# PCB_Motor_Sheet1.net
KiCad netlist of a schematic drawn in Altium Designer
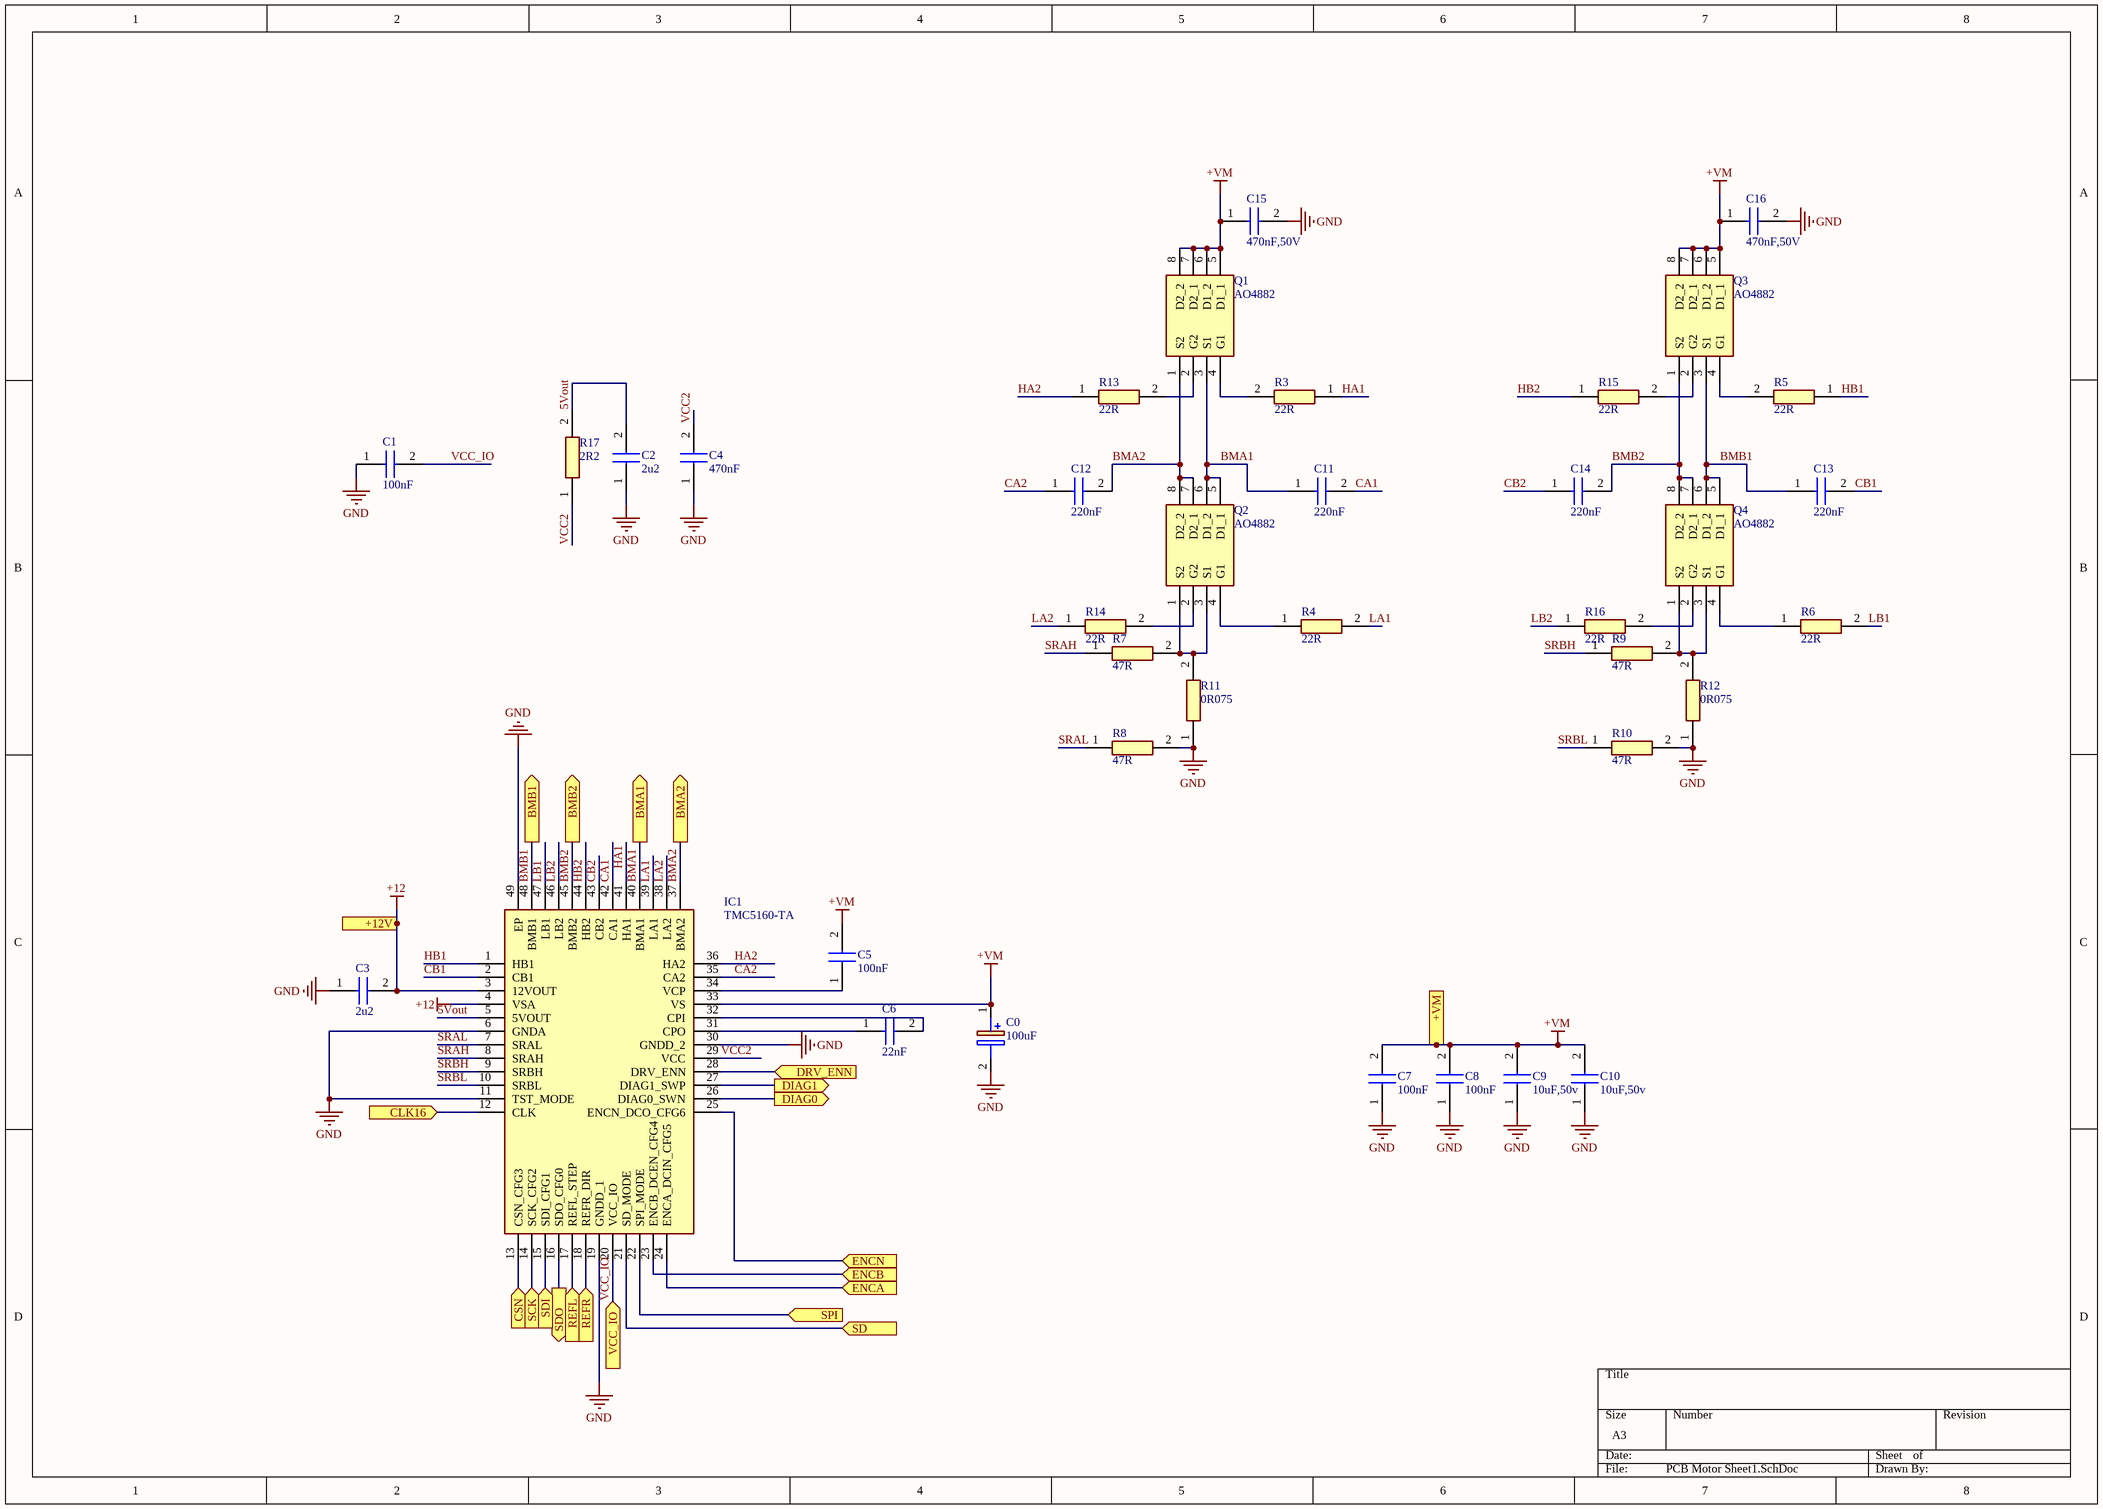
[diagram p0: PCB Motor Sheet1.SchDoc]

(export (version "E")
  (design (tool "Eeschema 10.0.6"))
  (components
    (comp (ref "C0")
      (value "100uF")
      (footprint "SamacSys:CAPAE850X1050N")
      (description "Capacitor Polarised\r\nMAL215097011E3")
      (fields
        (field (name "MANUFACTURER_PART_NUMBER") "MAL215097011E3")
        (field (name "MOUSER PART NUMBER") "594-MAL215097011E3")
      )
      (libsource (lib "*") (part "MAL215097011E3"))
    )
    (comp (ref "C1")
      (value "100nF")
      (footprint "SamacSys:CAPC1608X90N")
      (description "Capacitor")
      (fields
        (field (name "MANUFACTURER_PART_NUMBER") "GCM188R71H224KA64D")
        (field (name "MOUSER PART NUMBER") "81-GCM188R71H224K64D")
      )
      (libsource (lib "*") (part "GCM188R71H224KA64D"))
    )
    (comp (ref "C2")
      (value "2u2")
      (footprint "SamacSys:CAPC1608X90N")
      (description "Capacitor")
      (fields
        (field (name "MANUFACTURER_PART_NUMBER") "GCM188R71H224KA64D")
        (field (name "MOUSER PART NUMBER") "81-GCM188R71H224K64D")
      )
      (libsource (lib "*") (part "GCM188R71H224KA64D"))
    )
    (comp (ref "C3")
      (value "2u2")
      (footprint "SamacSys:CAPC1608X90N")
      (description "Capacitor")
      (fields
        (field (name "MANUFACTURER_PART_NUMBER") "GCM188R71H224KA64D")
        (field (name "MOUSER PART NUMBER") "81-GCM188R71H224K64D")
      )
      (libsource (lib "*") (part "GCM188R71H224KA64D"))
    )
    (comp (ref "C4")
      (value "470nF")
      (footprint "SamacSys:CAPC1608X90N")
      (description "Capacitor")
      (fields
        (field (name "MANUFACTURER_PART_NUMBER") "GCM188R71H224KA64D")
        (field (name "MOUSER PART NUMBER") "81-GCM188R71H224K64D")
      )
      (libsource (lib "*") (part "GCM188R71H224KA64D"))
    )
    (comp (ref "C5")
      (value "100nF")
      (footprint "SamacSys:CAPC1608X90N")
      (description "Capacitor")
      (fields
        (field (name "MANUFACTURER_PART_NUMBER") "GCM188R71H224KA64D")
        (field (name "MOUSER PART NUMBER") "81-GCM188R71H224K64D")
      )
      (libsource (lib "*") (part "GCM188R71H224KA64D"))
    )
    (comp (ref "C6")
      (value "22nF")
      (footprint "SamacSys:CAPC1608X90N")
      (description "Capacitor")
      (fields
        (field (name "MANUFACTURER_PART_NUMBER") "GCM188R71H224KA64D")
        (field (name "MOUSER PART NUMBER") "81-GCM188R71H224K64D")
      )
      (libsource (lib "*") (part "GCM188R71H224KA64D"))
    )
    (comp (ref "C7")
      (value "100nF")
      (footprint "SamacSys:CAPC1608X90N")
      (description "Capacitor")
      (fields
        (field (name "MANUFACTURER_PART_NUMBER") "GCM188R71H224KA64D")
        (field (name "MOUSER PART NUMBER") "81-GCM188R71H224K64D")
      )
      (libsource (lib "*") (part "GCM188R71H224KA64D"))
    )
    (comp (ref "C8")
      (value "100nF")
      (footprint "SamacSys:CAPC1608X90N")
      (description "Capacitor")
      (fields
        (field (name "MANUFACTURER_PART_NUMBER") "GCM188R71H224KA64D")
        (field (name "MOUSER PART NUMBER") "81-GCM188R71H224K64D")
      )
      (libsource (lib "*") (part "GCM188R71H224KA64D"))
    )
    (comp (ref "C9")
      (value "10uF,50v")
      (footprint "SamacSys:CAPC3216X180N")
      (description "Capacitor")
      (fields
        (field (name "MANUFACTURER_PART_NUMBER") "GRM31CR61H106MA12L")
        (field (name "MOUSER PART NUMBER") "81-GRM31CR61H106MA2L")
      )
      (libsource (lib "*") (part "GRM31CR61H106MA12L"))
    )
    (comp (ref "C10")
      (value "10uF,50v")
      (footprint "SamacSys:CAPC3216X180N")
      (description "Capacitor")
      (fields
        (field (name "MANUFACTURER_PART_NUMBER") "GRM31CR61H106MA12L")
        (field (name "MOUSER PART NUMBER") "81-GRM31CR61H106MA2L")
      )
      (libsource (lib "*") (part "GRM31CR61H106MA12L"))
    )
    (comp (ref "C11")
      (value "220nF")
      (footprint "SamacSys:CAPC1608X90N")
      (description "Capacitor")
      (fields
        (field (name "MANUFACTURER_PART_NUMBER") "GCM188R71H224KA64D")
        (field (name "MOUSER PART NUMBER") "81-GCM188R71H224K64D")
      )
      (libsource (lib "*") (part "GCM188R71H224KA64D"))
    )
    (comp (ref "C12")
      (value "220nF")
      (footprint "SamacSys:CAPC1608X90N")
      (description "Capacitor")
      (fields
        (field (name "MANUFACTURER_PART_NUMBER") "GCM188R71H224KA64D")
        (field (name "MOUSER PART NUMBER") "81-GCM188R71H224K64D")
      )
      (libsource (lib "*") (part "GCM188R71H224KA64D"))
    )
    (comp (ref "C13")
      (value "220nF")
      (footprint "SamacSys:CAPC1608X90N")
      (description "Capacitor")
      (fields
        (field (name "MANUFACTURER_PART_NUMBER") "GCM188R71H224KA64D")
        (field (name "MOUSER PART NUMBER") "81-GCM188R71H224K64D")
      )
      (libsource (lib "*") (part "GCM188R71H224KA64D"))
    )
    (comp (ref "C14")
      (value "220nF")
      (footprint "SamacSys:CAPC1608X90N")
      (description "Capacitor")
      (fields
        (field (name "MANUFACTURER_PART_NUMBER") "GCM188R71H224KA64D")
        (field (name "MOUSER PART NUMBER") "81-GCM188R71H224K64D")
      )
      (libsource (lib "*") (part "GCM188R71H224KA64D"))
    )
    (comp (ref "C15")
      (value "470nF,50V")
      (footprint "SamacSys:C1608_Commercial")
      (description "Capacitor")
      (fields
        (field (name "MANUFACTURER_PART_NUMBER") "C1608X7R1H474K080AC")
        (field (name "MOUSER PART NUMBER") "810-C1608X7R1H474K")
      )
      (libsource (lib "*") (part "C1608X7R1H474K080AC"))
    )
    (comp (ref "C16")
      (value "470nF,50V")
      (footprint "SamacSys:C1608_Commercial")
      (description "Capacitor")
      (fields
        (field (name "MANUFACTURER_PART_NUMBER") "C1608X7R1H474K080AC")
        (field (name "MOUSER PART NUMBER") "810-C1608X7R1H474K")
      )
      (libsource (lib "*") (part "C1608X7R1H474K080AC"))
    )
    (comp (ref "IC1")
      (value "TMC5160-TA")
      (footprint "SamacSys:QFP50P900X900X120-49N")
      (description "Integrated Circuit")
      (fields (field (name "LCSC PART #") "C516354"))
      (libsource (lib "*") (part "TMC5160-TA"))
    )
    (comp (ref "Q1")
      (value "AO4882")
      (footprint "SamacSys:SOIC127P600X175-8N")
      (description "MOSFET (N-Channel)")
      (fields (field (name "LCSC PART #") "C3040598"))
      (libsource (lib "*") (part "AO4882"))
    )
    (comp (ref "Q2")
      (value "AO4882")
      (footprint "SamacSys:SOIC127P600X175-8N")
      (description "MOSFET (N-Channel)")
      (fields (field (name "LCSC PART #") "C3040598"))
      (libsource (lib "*") (part "AO4882"))
    )
    (comp (ref "Q3")
      (value "AO4882")
      (footprint "SamacSys:SOIC127P600X175-8N")
      (description "MOSFET (N-Channel)")
      (fields (field (name "LCSC PART #") "C3040598"))
      (libsource (lib "*") (part "AO4882"))
    )
    (comp (ref "Q4")
      (value "AO4882")
      (footprint "SamacSys:SOIC127P600X175-8N")
      (description "MOSFET (N-Channel)")
      (fields (field (name "LCSC PART #") "C3040598"))
      (libsource (lib "*") (part "AO4882"))
    )
    (comp (ref "R3")
      (value "22R")
      (footprint "SamacSys:RESC1608X55N")
      (description "Resistor")
      (fields
        (field (name "MANUFACTURER_PART_NUMBER") "MC0063W06031100K")
        (field (name "LCSC PART #") "C122707")
      )
      (libsource (lib "") (part "MC0063W06031100K_2"))
    )
    (comp (ref "R4")
      (value "22R")
      (footprint "SamacSys:RESC1608X55N")
      (description "Resistor")
      (fields
        (field (name "MANUFACTURER_PART_NUMBER") "MC0063W06031100K")
        (field (name "LCSC PART #") "C122707")
      )
      (libsource (lib "*") (part "MC0063W06031100K"))
    )
    (comp (ref "R5")
      (value "22R")
      (footprint "SamacSys:RESC1608X55N")
      (description "Resistor")
      (fields
        (field (name "MANUFACTURER_PART_NUMBER") "MC0063W06031100K")
        (field (name "LCSC PART #") "C122707")
      )
      (libsource (lib "") (part "MC0063W06031100K_2"))
    )
    (comp (ref "R6")
      (value "22R")
      (footprint "SamacSys:RESC1608X55N")
      (description "Resistor")
      (fields
        (field (name "MANUFACTURER_PART_NUMBER") "MC0063W06031100K")
        (field (name "LCSC PART #") "C122707")
      )
      (libsource (lib "*") (part "MC0063W06031100K"))
    )
    (comp (ref "R7")
      (value "47R")
      (footprint "SamacSys:RESC1608X60N")
      (description "Resistor")
      (fields
        (field (name "MANUFACTURER_PART_NUMBER") "MCSR06X47R0FTL")
        (field (name "LCSC PART #") "C2136913")
      )
      (libsource (lib "*") (part "MCSR06X47R0FTL"))
    )
    (comp (ref "R8")
      (value "47R")
      (footprint "SamacSys:RESC1608X60N")
      (description "Resistor")
      (fields
        (field (name "MANUFACTURER_PART_NUMBER") "MCSR06X47R0FTL")
        (field (name "LCSC PART #") "C2136913")
      )
      (libsource (lib "*") (part "MCSR06X47R0FTL"))
    )
    (comp (ref "R9")
      (value "47R")
      (footprint "SamacSys:RESC1608X60N")
      (description "Resistor")
      (fields
        (field (name "MANUFACTURER_PART_NUMBER") "MCSR06X47R0FTL")
        (field (name "LCSC PART #") "C2136913")
      )
      (libsource (lib "*") (part "MCSR06X47R0FTL"))
    )
    (comp (ref "R10")
      (value "47R")
      (footprint "SamacSys:RESC1608X60N")
      (description "Resistor")
      (fields
        (field (name "MANUFACTURER_PART_NUMBER") "MCSR06X47R0FTL")
        (field (name "LCSC PART #") "C2136913")
      )
      (libsource (lib "*") (part "MCSR06X47R0FTL"))
    )
    (comp (ref "R11")
      (value "0R075")
      (footprint "SamacSys:ERJ8_B_BW_R_LW_CW_D")
      (description "Resistor")
      (fields
        (field (name "MANUFACTURER_PART_NUMBER") "ERJ-8BWFR075V")
        (field (name "MOUSER PART NUMBER") "667-ERJ-8BWFR075V")
      )
      (libsource (lib "*") (part "ERJ-8BWFR075V"))
    )
    (comp (ref "R12")
      (value "0R075")
      (footprint "SamacSys:ERJ8_B_BW_R_LW_CW_D")
      (description "Resistor")
      (fields
        (field (name "MANUFACTURER_PART_NUMBER") "ERJ-8BWFR075V")
        (field (name "MOUSER PART NUMBER") "667-ERJ-8BWFR075V")
      )
      (libsource (lib "*") (part "ERJ-8BWFR075V"))
    )
    (comp (ref "R13")
      (value "22R")
      (footprint "SamacSys:RESC1608X55N")
      (description "Resistor")
      (fields
        (field (name "MANUFACTURER_PART_NUMBER") "MC0063W06031100K")
        (field (name "LCSC PART #") "C122707")
      )
      (libsource (lib "*") (part "MC0063W06031100K"))
    )
    (comp (ref "R14")
      (value "22R")
      (footprint "SamacSys:RESC1608X55N")
      (description "Resistor")
      (fields
        (field (name "MANUFACTURER_PART_NUMBER") "MC0063W06031100K")
        (field (name "LCSC PART #") "C122707")
      )
      (libsource (lib "*") (part "MC0063W06031100K"))
    )
    (comp (ref "R15")
      (value "22R")
      (footprint "SamacSys:RESC1608X55N")
      (description "Resistor")
      (fields
        (field (name "MANUFACTURER_PART_NUMBER") "MC0063W06031100K")
        (field (name "LCSC PART #") "C122707")
      )
      (libsource (lib "*") (part "MC0063W06031100K"))
    )
    (comp (ref "R16")
      (value "22R")
      (footprint "SamacSys:RESC1608X55N")
      (description "Resistor")
      (fields
        (field (name "MANUFACTURER_PART_NUMBER") "MC0063W06031100K")
        (field (name "LCSC PART #") "C122707")
      )
      (libsource (lib "*") (part "MC0063W06031100K"))
    )
    (comp (ref "R17")
      (value "2R2")
      (footprint "SamacSys:RESC1608X55N")
      (description "Resistor")
      (fields
        (field (name "MANUFACTURER_PART_NUMBER") "MC0063W06031100K")
        (field (name "LCSC PART #") "C269422")
      )
      (libsource (lib "") (part "MC0063W06031100K_1"))
    )
  )
  (nets
    (net (code "1") (name "+12") (class "Default")
      (node (ref "C3") (pin "2") (pinfunction "2_2") (pintype "passive"))
      (node (ref "IC1") (pin "3") (pinfunction "12VOUT_3") (pintype "passive"))
      (node (ref "IC1") (pin "4") (pinfunction "VSA_4") (pintype "passive"))
    )
    (net (code "2") (name "+VM") (class "Default")
      (node (ref "C0") (pin "1") (pinfunction "+_1") (pintype "passive"))
      (node (ref "C10") (pin "2") (pinfunction "2_2") (pintype "passive"))
      (node (ref "C15") (pin "1") (pinfunction "1_1") (pintype "passive"))
      (node (ref "C16") (pin "1") (pinfunction "1_1") (pintype "passive"))
      (node (ref "C5") (pin "2") (pinfunction "2_2") (pintype "passive"))
      (node (ref "C7") (pin "2") (pinfunction "2_2") (pintype "passive"))
      (node (ref "C8") (pin "2") (pinfunction "2_2") (pintype "passive"))
      (node (ref "C9") (pin "2") (pinfunction "2_2") (pintype "passive"))
      (node (ref "IC1") (pin "33") (pinfunction "VS_33") (pintype "passive"))
      (node (ref "Q1") (pin "5") (pinfunction "D1_1_5") (pintype "passive"))
      (node (ref "Q1") (pin "6") (pinfunction "D1_2_6") (pintype "passive"))
      (node (ref "Q1") (pin "7") (pinfunction "D2_1_7") (pintype "passive"))
      (node (ref "Q1") (pin "8") (pinfunction "D2_2_8") (pintype "passive"))
      (node (ref "Q3") (pin "5") (pinfunction "D1_1_5") (pintype "passive"))
      (node (ref "Q3") (pin "6") (pinfunction "D1_2_6") (pintype "passive"))
      (node (ref "Q3") (pin "7") (pinfunction "D2_1_7") (pintype "passive"))
      (node (ref "Q3") (pin "8") (pinfunction "D2_2_8") (pintype "passive"))
    )
    (net (code "3") (name "/5Vout") (class "Default")
      (node (ref "C2") (pin "2") (pinfunction "2_2") (pintype "passive"))
      (node (ref "IC1") (pin "5") (pinfunction "5VOUT_5") (pintype "passive"))
      (node (ref "R17") (pin "2") (pinfunction "2_2") (pintype "passive"))
    )
    (net (code "4") (name "/BMA1") (class "Default")
      (node (ref "C11") (pin "1") (pinfunction "1_1") (pintype "passive"))
      (node (ref "IC1") (pin "40") (pinfunction "BMA1_40") (pintype "passive"))
      (node (ref "Q1") (pin "3") (pinfunction "S1_3") (pintype "passive"))
      (node (ref "Q2") (pin "5") (pinfunction "D1_1_5") (pintype "passive"))
      (node (ref "Q2") (pin "6") (pinfunction "D1_2_6") (pintype "passive"))
    )
    (net (code "5") (name "/BMA2") (class "Default")
      (node (ref "C12") (pin "2") (pinfunction "2_2") (pintype "passive"))
      (node (ref "IC1") (pin "37") (pinfunction "BMA2_37") (pintype "passive"))
      (node (ref "Q1") (pin "1") (pinfunction "S2_1") (pintype "passive"))
      (node (ref "Q2") (pin "7") (pinfunction "D2_1_7") (pintype "passive"))
      (node (ref "Q2") (pin "8") (pinfunction "D2_2_8") (pintype "passive"))
    )
    (net (code "6") (name "/BMB1") (class "Default")
      (node (ref "C13") (pin "1") (pinfunction "1_1") (pintype "passive"))
      (node (ref "IC1") (pin "48") (pinfunction "BMB1_48") (pintype "passive"))
      (node (ref "Q3") (pin "3") (pinfunction "S1_3") (pintype "passive"))
      (node (ref "Q4") (pin "5") (pinfunction "D1_1_5") (pintype "passive"))
      (node (ref "Q4") (pin "6") (pinfunction "D1_2_6") (pintype "passive"))
    )
    (net (code "7") (name "/BMB2") (class "Default")
      (node (ref "C14") (pin "2") (pinfunction "2_2") (pintype "passive"))
      (node (ref "IC1") (pin "45") (pinfunction "BMB2_45") (pintype "passive"))
      (node (ref "Q3") (pin "1") (pinfunction "S2_1") (pintype "passive"))
      (node (ref "Q4") (pin "7") (pinfunction "D2_1_7") (pintype "passive"))
      (node (ref "Q4") (pin "8") (pinfunction "D2_2_8") (pintype "passive"))
    )
    (net (code "8") (name "/CA1") (class "Default")
      (node (ref "C11") (pin "2") (pinfunction "2_2") (pintype "passive"))
      (node (ref "IC1") (pin "42") (pinfunction "CA1_42") (pintype "passive"))
    )
    (net (code "9") (name "/CA2") (class "Default")
      (node (ref "C12") (pin "1") (pinfunction "1_1") (pintype "passive"))
      (node (ref "IC1") (pin "35") (pinfunction "CA2_35") (pintype "passive"))
    )
    (net (code "10") (name "/CB1") (class "Default")
      (node (ref "C13") (pin "2") (pinfunction "2_2") (pintype "passive"))
      (node (ref "IC1") (pin "2") (pinfunction "CB1_2") (pintype "passive"))
    )
    (net (code "11") (name "/CB2") (class "Default")
      (node (ref "C14") (pin "1") (pinfunction "1_1") (pintype "passive"))
      (node (ref "IC1") (pin "43") (pinfunction "CB2_43") (pintype "passive"))
    )
    (net (code "12") (name "/CLK16") (class "Default")
      (node (ref "IC1") (pin "12") (pinfunction "CLK_12") (pintype "passive"))
    )
    (net (code "13") (name "/CSN") (class "Default")
      (node (ref "IC1") (pin "13") (pinfunction "CSN_CFG3_13") (pintype "passive"))
    )
    (net (code "14") (name "/DIAG0") (class "Default")
      (node (ref "IC1") (pin "26") (pinfunction "DIAG0_SWN_26") (pintype "passive"))
    )
    (net (code "15") (name "/DIAG1") (class "Default")
      (node (ref "IC1") (pin "27") (pinfunction "DIAG1_SWP_27") (pintype "passive"))
    )
    (net (code "16") (name "/DRV_ENN") (class "Default")
      (node (ref "IC1") (pin "28") (pinfunction "DRV_ENN_28") (pintype "passive"))
    )
    (net (code "17") (name "/ENCA") (class "Default")
      (node (ref "IC1") (pin "24") (pinfunction "ENCA_DCIN_CFG5_24") (pintype "passive"))
    )
    (net (code "18") (name "/ENCB") (class "Default")
      (node (ref "IC1") (pin "23") (pinfunction "ENCB_DCEN_CFG4_23") (pintype "passive"))
    )
    (net (code "19") (name "/ENCN") (class "Default")
      (node (ref "IC1") (pin "25") (pinfunction "ENCN_DCO_CFG6_25") (pintype "passive"))
    )
    (net (code "20") (name "/HA1") (class "Default")
      (node (ref "IC1") (pin "41") (pinfunction "HA1_41") (pintype "passive"))
      (node (ref "R3") (pin "1") (pinfunction "1_1") (pintype "passive"))
    )
    (net (code "21") (name "/HA2") (class "Default")
      (node (ref "IC1") (pin "36") (pinfunction "HA2_36") (pintype "passive"))
      (node (ref "R13") (pin "1") (pinfunction "1_1") (pintype "passive"))
    )
    (net (code "22") (name "/HB1") (class "Default")
      (node (ref "IC1") (pin "1") (pinfunction "HB1_1") (pintype "passive"))
      (node (ref "R5") (pin "1") (pinfunction "1_1") (pintype "passive"))
    )
    (net (code "23") (name "/HB2") (class "Default")
      (node (ref "IC1") (pin "44") (pinfunction "HB2_44") (pintype "passive"))
      (node (ref "R15") (pin "1") (pinfunction "1_1") (pintype "passive"))
    )
    (net (code "24") (name "/LA1") (class "Default")
      (node (ref "IC1") (pin "39") (pinfunction "LA1_39") (pintype "passive"))
      (node (ref "R4") (pin "2") (pinfunction "2_2") (pintype "passive"))
    )
    (net (code "25") (name "/LA2") (class "Default")
      (node (ref "IC1") (pin "38") (pinfunction "LA2_38") (pintype "passive"))
      (node (ref "R14") (pin "1") (pinfunction "1_1") (pintype "passive"))
    )
    (net (code "26") (name "/LB1") (class "Default")
      (node (ref "IC1") (pin "47") (pinfunction "LB1_47") (pintype "passive"))
      (node (ref "R6") (pin "2") (pinfunction "2_2") (pintype "passive"))
    )
    (net (code "27") (name "/LB2") (class "Default")
      (node (ref "IC1") (pin "46") (pinfunction "LB2_46") (pintype "passive"))
      (node (ref "R16") (pin "1") (pinfunction "1_1") (pintype "passive"))
    )
    (net (code "28") (name "/REFL") (class "Default")
      (node (ref "IC1") (pin "17") (pinfunction "REFL_STEP_17") (pintype "passive"))
    )
    (net (code "29") (name "/REFR") (class "Default")
      (node (ref "IC1") (pin "18") (pinfunction "REFR_DIR_18") (pintype "passive"))
    )
    (net (code "30") (name "/SCK") (class "Default")
      (node (ref "IC1") (pin "14") (pinfunction "SCK_CFG2_14") (pintype "passive"))
    )
    (net (code "31") (name "/SD") (class "Default")
      (node (ref "IC1") (pin "21") (pinfunction "SD_MODE_21") (pintype "passive"))
    )
    (net (code "32") (name "/SDI") (class "Default")
      (node (ref "IC1") (pin "15") (pinfunction "SDI_CFG1_15") (pintype "passive"))
    )
    (net (code "33") (name "/SDO") (class "Default")
      (node (ref "IC1") (pin "16") (pinfunction "SDO_CFG0_16") (pintype "passive"))
    )
    (net (code "34") (name "/SPI") (class "Default")
      (node (ref "IC1") (pin "22") (pinfunction "SPI_MODE_22") (pintype "passive"))
    )
    (net (code "35") (name "/SRAH") (class "Default")
      (node (ref "IC1") (pin "8") (pinfunction "SRAH_8") (pintype "passive"))
      (node (ref "R7") (pin "1") (pinfunction "1_1") (pintype "passive"))
    )
    (net (code "36") (name "/SRAL") (class "Default")
      (node (ref "IC1") (pin "7") (pinfunction "SRAL_7") (pintype "passive"))
      (node (ref "R8") (pin "1") (pinfunction "1_1") (pintype "passive"))
    )
    (net (code "37") (name "/SRBH") (class "Default")
      (node (ref "IC1") (pin "9") (pinfunction "SRBH_9") (pintype "passive"))
      (node (ref "R9") (pin "1") (pinfunction "1_1") (pintype "passive"))
    )
    (net (code "38") (name "/SRBL") (class "Default")
      (node (ref "IC1") (pin "10") (pinfunction "SRBL_10") (pintype "passive"))
      (node (ref "R10") (pin "1") (pinfunction "1_1") (pintype "passive"))
    )
    (net (code "39") (name "/VCC1") (class "Default")
      (node (ref "C4") (pin "2") (pinfunction "2_2") (pintype "passive"))
      (node (ref "IC1") (pin "29") (pinfunction "VCC_29") (pintype "passive"))
      (node (ref "R17") (pin "1") (pinfunction "1_1") (pintype "passive"))
    )
    (net (code "40") (name "/VCC_IO") (class "Default")
      (node (ref "C1") (pin "2") (pinfunction "2_2") (pintype "passive"))
      (node (ref "IC1") (pin "20") (pinfunction "VCC_IO_20") (pintype "passive"))
    )
    (net (code "41") (name "GND") (class "Default")
      (node (ref "C0") (pin "2") (pinfunction "-_2") (pintype "passive"))
      (node (ref "C1") (pin "1") (pinfunction "1_1") (pintype "passive"))
      (node (ref "C10") (pin "1") (pinfunction "1_1") (pintype "passive"))
      (node (ref "C15") (pin "2") (pinfunction "2_2") (pintype "passive"))
      (node (ref "C16") (pin "2") (pinfunction "2_2") (pintype "passive"))
      (node (ref "C2") (pin "1") (pinfunction "1_1") (pintype "passive"))
      (node (ref "C3") (pin "1") (pinfunction "1_1") (pintype "passive"))
      (node (ref "C4") (pin "1") (pinfunction "1_1") (pintype "passive"))
      (node (ref "C7") (pin "1") (pinfunction "1_1") (pintype "passive"))
      (node (ref "C8") (pin "1") (pinfunction "1_1") (pintype "passive"))
      (node (ref "C9") (pin "1") (pinfunction "1_1") (pintype "passive"))
      (node (ref "IC1") (pin "11") (pinfunction "TST_MODE_11") (pintype "passive"))
      (node (ref "IC1") (pin "19") (pinfunction "GNDD_1_19") (pintype "passive"))
      (node (ref "IC1") (pin "30") (pinfunction "GNDD_2_30") (pintype "passive"))
      (node (ref "IC1") (pin "49") (pinfunction "EP_49") (pintype "passive"))
      (node (ref "IC1") (pin "6") (pinfunction "GNDA_6") (pintype "passive"))
      (node (ref "R10") (pin "2") (pinfunction "2_2") (pintype "passive"))
      (node (ref "R11") (pin "1") (pinfunction "1_1") (pintype "passive"))
      (node (ref "R12") (pin "1") (pinfunction "1_1") (pintype "passive"))
      (node (ref "R8") (pin "2") (pinfunction "2_2") (pintype "passive"))
    )
    (net (code "42") (name "Net-(IC1-CPI)") (class "Default")
      (node (ref "C6") (pin "2") (pinfunction "2_2") (pintype "passive"))
      (node (ref "IC1") (pin "32") (pinfunction "CPI_32") (pintype "passive"))
    )
    (net (code "43") (name "Net-(IC1-CPO)") (class "Default")
      (node (ref "C6") (pin "1") (pinfunction "1_1") (pintype "passive"))
      (node (ref "IC1") (pin "31") (pinfunction "CPO_31") (pintype "passive"))
    )
    (net (code "44") (name "Net-(IC1-VCP)") (class "Default")
      (node (ref "C5") (pin "1") (pinfunction "1_1") (pintype "passive"))
      (node (ref "IC1") (pin "34") (pinfunction "VCP_34") (pintype "passive"))
    )
    (net (code "45") (name "Net-(Q1-G1)") (class "Default")
      (node (ref "Q1") (pin "4") (pinfunction "G1_4") (pintype "passive"))
      (node (ref "R3") (pin "2") (pinfunction "2_2") (pintype "passive"))
    )
    (net (code "46") (name "Net-(Q1-G2)") (class "Default")
      (node (ref "Q1") (pin "2") (pinfunction "G2_2") (pintype "passive"))
      (node (ref "R13") (pin "2") (pinfunction "2_2") (pintype "passive"))
    )
    (net (code "47") (name "Net-(Q2-G1)") (class "Default")
      (node (ref "Q2") (pin "4") (pinfunction "G1_4") (pintype "passive"))
      (node (ref "R4") (pin "1") (pinfunction "1_1") (pintype "passive"))
    )
    (net (code "48") (name "Net-(Q2-G2)") (class "Default")
      (node (ref "Q2") (pin "2") (pinfunction "G2_2") (pintype "passive"))
      (node (ref "R14") (pin "2") (pinfunction "2_2") (pintype "passive"))
    )
    (net (code "49") (name "Net-(Q2-S1)") (class "Default")
      (node (ref "Q2") (pin "1") (pinfunction "S2_1") (pintype "passive"))
      (node (ref "Q2") (pin "3") (pinfunction "S1_3") (pintype "passive"))
      (node (ref "R11") (pin "2") (pinfunction "2_2") (pintype "passive"))
      (node (ref "R7") (pin "2") (pinfunction "2_2") (pintype "passive"))
    )
    (net (code "50") (name "Net-(Q3-G1)") (class "Default")
      (node (ref "Q3") (pin "4") (pinfunction "G1_4") (pintype "passive"))
      (node (ref "R5") (pin "2") (pinfunction "2_2") (pintype "passive"))
    )
    (net (code "51") (name "Net-(Q3-G2)") (class "Default")
      (node (ref "Q3") (pin "2") (pinfunction "G2_2") (pintype "passive"))
      (node (ref "R15") (pin "2") (pinfunction "2_2") (pintype "passive"))
    )
    (net (code "52") (name "Net-(Q4-G1)") (class "Default")
      (node (ref "Q4") (pin "4") (pinfunction "G1_4") (pintype "passive"))
      (node (ref "R6") (pin "1") (pinfunction "1_1") (pintype "passive"))
    )
    (net (code "53") (name "Net-(Q4-G2)") (class "Default")
      (node (ref "Q4") (pin "2") (pinfunction "G2_2") (pintype "passive"))
      (node (ref "R16") (pin "2") (pinfunction "2_2") (pintype "passive"))
    )
    (net (code "54") (name "Net-(Q4-S1)") (class "Default")
      (node (ref "Q4") (pin "1") (pinfunction "S2_1") (pintype "passive"))
      (node (ref "Q4") (pin "3") (pinfunction "S1_3") (pintype "passive"))
      (node (ref "R12") (pin "2") (pinfunction "2_2") (pintype "passive"))
      (node (ref "R9") (pin "2") (pinfunction "2_2") (pintype "passive"))
    )
  )
)
